# rapidshark-main-breakout-top-mk-1_4.net
KiCad netlist of a schematic drawn in EAGLE
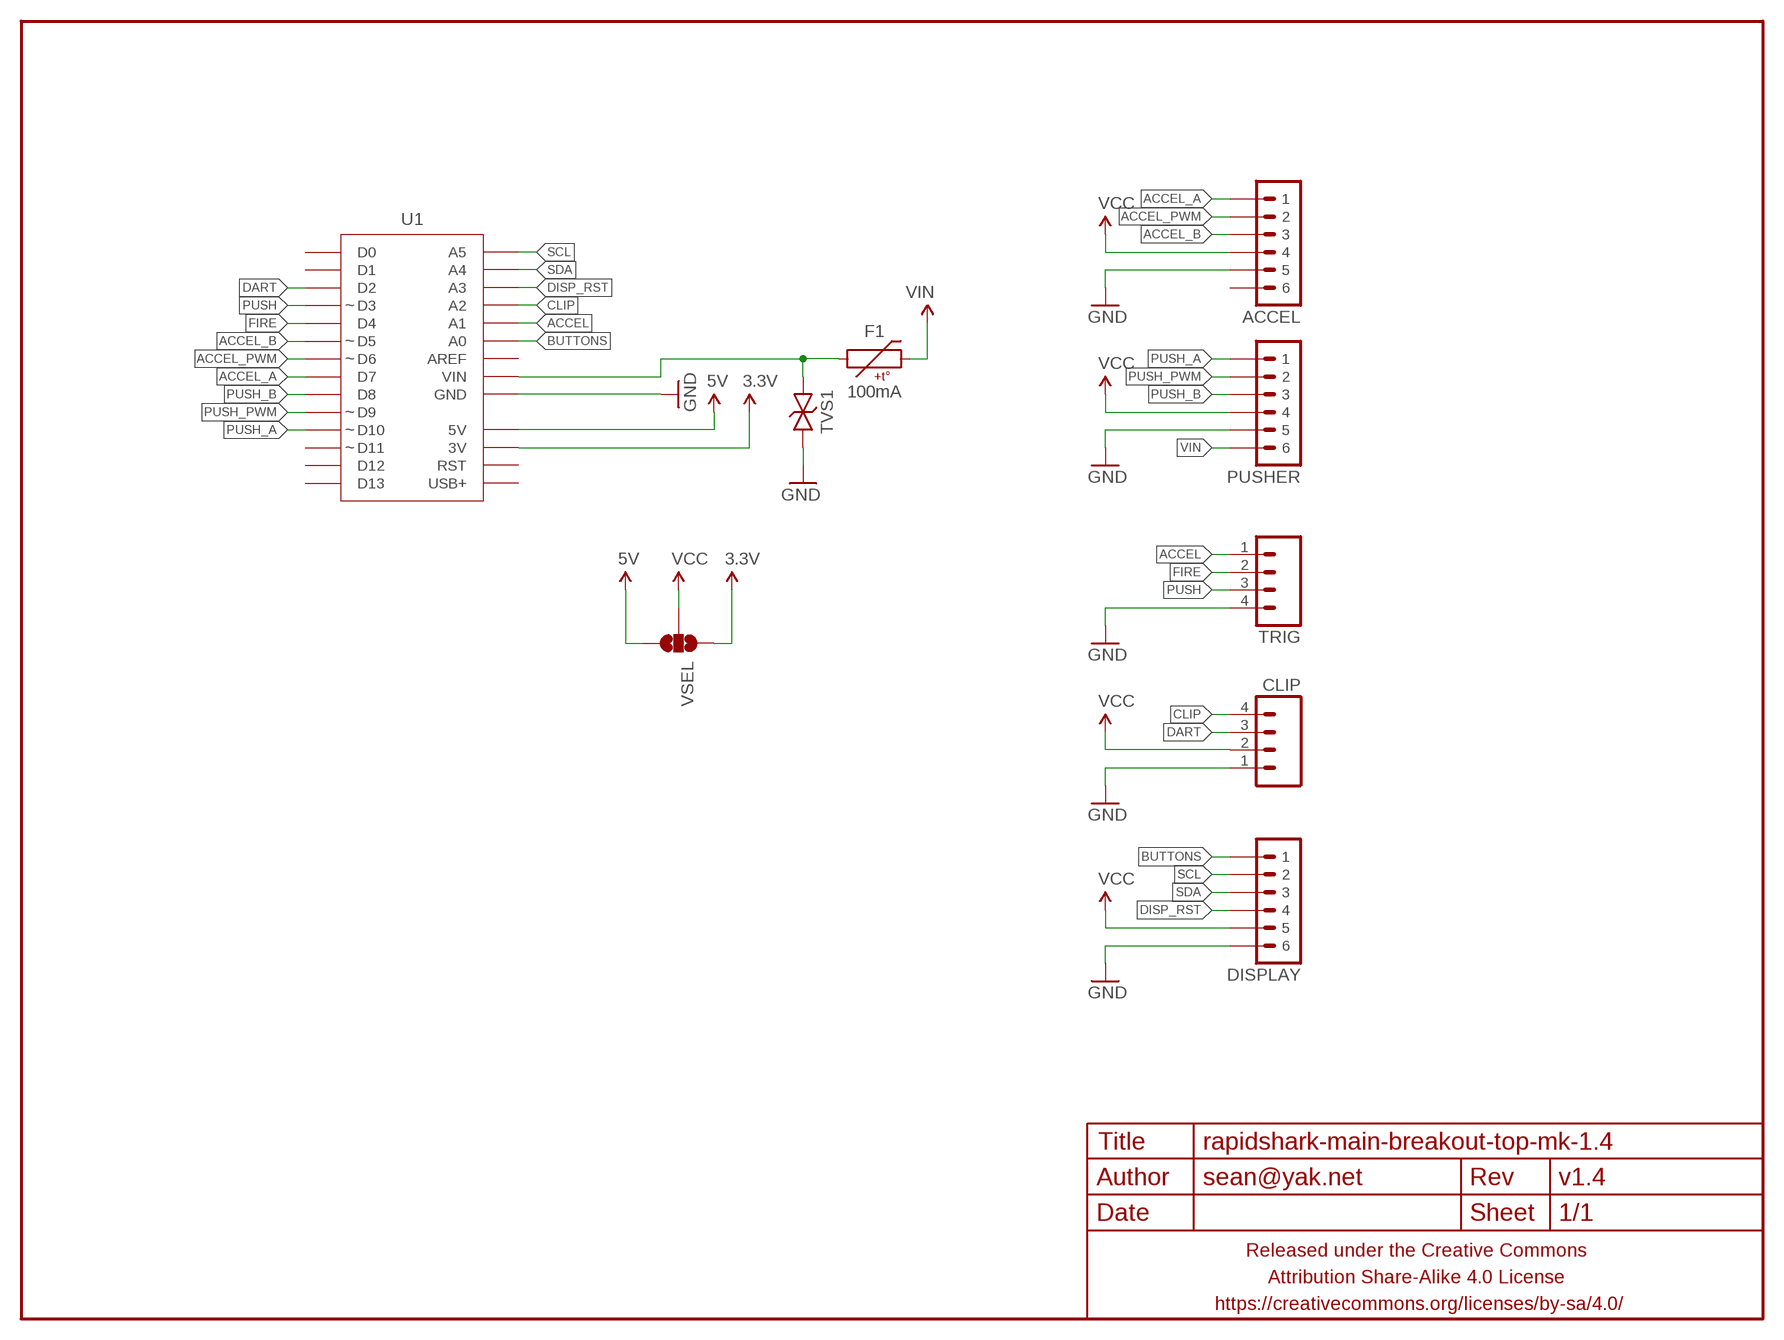
[diagram p0: schematic, sheet 1]

(export (version "E")
  (design (tool "Eeschema 10.0.6"))
  (components
    (comp (ref "ACCEL")
      (value "M06JST-PH-PTH-VERT")
      (footprint "eagle-import:JST-6-PH-VERT-PTH")
      (libsource (lib "eagle-import") (part "M06JST-PH-PTH-VERT"))
    )
    (comp (ref "CLIP")
      (value "M04JST-PTH-VERT")
      (footprint "eagle-import:JST-4-PH-VERT-PTH")
      (libsource (lib "eagle-import") (part "M04JST-PTH-VERT"))
    )
    (comp (ref "DISPLAY")
      (value "M06JST-PH-PTH-VERT")
      (footprint "eagle-import:JST-6-PH-VERT-PTH")
      (libsource (lib "eagle-import") (part "M06JST-PH-PTH-VERT"))
    )
    (comp (ref "F1")
      (value "100mA")
      (footprint "eagle-import:PTC-1206")
      (libsource (lib "eagle-import") (part "PTCSMD"))
    )
    (comp (ref "FRAME1")
      (value "FRAME-LETTERNO_PACKAGE")
      (footprint "eagle-import:DUMMY")
      (fields (field (name "DESIGNER") "sean@yak.net") (field (name "VERSION") "v1.4"))
      (libsource (lib "eagle-import") (part "FRAME-LETTERNO_PACKAGE"))
    )
    (comp (ref "PUSHER")
      (value "M06JST-PH-PTH-VERT")
      (footprint "eagle-import:JST-6-PH-VERT-PTH")
      (libsource (lib "eagle-import") (part "M06JST-PH-PTH-VERT"))
    )
    (comp (ref "TRIG")
      (value "M04JST-PTH-VERT")
      (footprint "eagle-import:JST-4-PH-VERT-PTH")
      (libsource (lib "eagle-import") (part "M04JST-PTH-VERT"))
    )
    (comp (ref "TVS1")
      (value "TVSDO-41-8.89MM")
      (footprint "eagle-import:DO-41-TVS-BI-8.89MM")
      (libsource (lib "eagle-import") (part "TVSDO-41-8.89MM"))
    )
    (comp (ref "U1")
      (value "ADAFRUIT_METRO_MININOSILK-AMBI2")
      (footprint "eagle-import:ADAFRUIT_METRO_MINI_BACK")
      (libsource (lib "eagle-import") (part "ADAFRUIT_METRO_MININOSILK-AMBI2"))
    )
    (comp (ref "VSEL")
      (value "JUMPER-PAD-3-NOFULL_BOX_SILK")
      (footprint "eagle-import:PAD-JUMPER-3-NO_YES_SILK_FULL_BOX")
      (libsource (lib "eagle-import") (part "JUMPER-PAD-3-NOFULL_BOX_SILK"))
    )
  )
  (nets
    (net (code "1") (name "3.3V") (class "Default")
      (node (ref "U1") (pin "17") (pinfunction "3V_17") (pintype "bidirectional"))
      (node (ref "VSEL") (pin "1") (pinfunction "1_1") (pintype "passive"))
    )
    (net (code "2") (name "5V") (class "Default")
      (node (ref "U1") (pin "18") (pinfunction "5V_18") (pintype "bidirectional"))
      (node (ref "VSEL") (pin "3") (pinfunction "3_3") (pintype "passive"))
    )
    (net (code "3") (name "ACCEL") (class "Default")
      (node (ref "TRIG") (pin "1") (pinfunction "1_1") (pintype "passive"))
      (node (ref "U1") (pin "24") (pinfunction "A1_24") (pintype "bidirectional"))
    )
    (net (code "4") (name "ACCEL_A") (class "Default")
      (node (ref "ACCEL") (pin "1") (pinfunction "1_1") (pintype "passive"))
      (node (ref "U1") (pin "8") (pinfunction "D7_8") (pintype "bidirectional"))
    )
    (net (code "5") (name "ACCEL_B") (class "Default")
      (node (ref "ACCEL") (pin "3") (pinfunction "3_3") (pintype "passive"))
      (node (ref "U1") (pin "6") (pinfunction "D5_6") (pintype "bidirectional"))
    )
    (net (code "6") (name "ACCEL_PWM") (class "Default")
      (node (ref "ACCEL") (pin "2") (pinfunction "2_2") (pintype "passive"))
      (node (ref "U1") (pin "7") (pinfunction "D6_7") (pintype "bidirectional"))
    )
    (net (code "7") (name "BUTTONS") (class "Default")
      (node (ref "DISPLAY") (pin "1") (pinfunction "1_1") (pintype "passive"))
      (node (ref "U1") (pin "23") (pinfunction "A0_23") (pintype "bidirectional"))
    )
    (net (code "8") (name "CLIP") (class "Default")
      (node (ref "CLIP") (pin "4") (pinfunction "4_4") (pintype "passive"))
      (node (ref "U1") (pin "25") (pinfunction "A2_25") (pintype "bidirectional"))
    )
    (net (code "9") (name "DART") (class "Default")
      (node (ref "CLIP") (pin "3") (pinfunction "3_3") (pintype "passive"))
      (node (ref "U1") (pin "3") (pinfunction "D2_3") (pintype "bidirectional"))
    )
    (net (code "10") (name "DISP_RST") (class "Default")
      (node (ref "DISPLAY") (pin "4") (pinfunction "4_4") (pintype "passive"))
      (node (ref "U1") (pin "26") (pinfunction "A3_26") (pintype "bidirectional"))
    )
    (net (code "11") (name "FIRE") (class "Default")
      (node (ref "TRIG") (pin "2") (pinfunction "2_2") (pintype "passive"))
      (node (ref "U1") (pin "5") (pinfunction "D4_5") (pintype "bidirectional"))
    )
    (net (code "12") (name "GND") (class "Default")
      (node (ref "ACCEL") (pin "5") (pinfunction "5_5") (pintype "passive"))
      (node (ref "CLIP") (pin "1") (pinfunction "1_1") (pintype "passive"))
      (node (ref "DISPLAY") (pin "6") (pinfunction "6_6") (pintype "passive"))
      (node (ref "PUSHER") (pin "5") (pinfunction "5_5") (pintype "passive"))
      (node (ref "TRIG") (pin "4") (pinfunction "4_4") (pintype "passive"))
      (node (ref "TVS1") (pin "P$1") (pinfunction "1_P$1") (pintype "passive"))
      (node (ref "U1") (pin "19") (pinfunction "GND_19") (pintype "bidirectional"))
      (node (ref "U1") (pin "20") (pinfunction "GND_20") (pintype "bidirectional"))
    )
    (net (code "13") (name "Net-(TVS1-2)") (class "Default")
      (node (ref "F1") (pin "1") (pinfunction "1_1") (pintype "passive"))
      (node (ref "TVS1") (pin "P$2") (pinfunction "2_P$2") (pintype "passive"))
      (node (ref "U1") (pin "21") (pinfunction "VIN_21") (pintype "bidirectional"))
    )
    (net (code "14") (name "PUSH") (class "Default")
      (node (ref "TRIG") (pin "3") (pinfunction "3_3") (pintype "passive"))
      (node (ref "U1") (pin "4") (pinfunction "D3_4") (pintype "bidirectional"))
    )
    (net (code "15") (name "PUSH_A") (class "Default")
      (node (ref "PUSHER") (pin "1") (pinfunction "1_1") (pintype "passive"))
      (node (ref "U1") (pin "11") (pinfunction "D10_11") (pintype "bidirectional"))
    )
    (net (code "16") (name "PUSH_B") (class "Default")
      (node (ref "PUSHER") (pin "3") (pinfunction "3_3") (pintype "passive"))
      (node (ref "U1") (pin "9") (pinfunction "D8_9") (pintype "bidirectional"))
    )
    (net (code "17") (name "PUSH_PWM") (class "Default")
      (node (ref "PUSHER") (pin "2") (pinfunction "2_2") (pintype "passive"))
      (node (ref "U1") (pin "10") (pinfunction "D9_10") (pintype "bidirectional"))
    )
    (net (code "18") (name "SCL") (class "Default")
      (node (ref "DISPLAY") (pin "2") (pinfunction "2_2") (pintype "passive"))
      (node (ref "U1") (pin "28") (pinfunction "A5_28") (pintype "bidirectional"))
    )
    (net (code "19") (name "SDA") (class "Default")
      (node (ref "DISPLAY") (pin "3") (pinfunction "3_3") (pintype "passive"))
      (node (ref "U1") (pin "27") (pinfunction "A4_27") (pintype "bidirectional"))
    )
    (net (code "20") (name "VCC") (class "Default")
      (node (ref "ACCEL") (pin "4") (pinfunction "4_4") (pintype "passive"))
      (node (ref "CLIP") (pin "2") (pinfunction "2_2") (pintype "passive"))
      (node (ref "DISPLAY") (pin "5") (pinfunction "5_5") (pintype "passive"))
      (node (ref "PUSHER") (pin "4") (pinfunction "4_4") (pintype "passive"))
      (node (ref "VSEL") (pin "2") (pinfunction "2_2") (pintype "passive"))
    )
    (net (code "21") (name "VIN") (class "Default")
      (node (ref "F1") (pin "2") (pinfunction "2_2") (pintype "passive"))
      (node (ref "PUSHER") (pin "6") (pinfunction "6_6") (pintype "passive"))
    )
    (net (code "22") (name "unconnected-(ACCEL-Pad6)") (class "Default")
      (node (ref "ACCEL") (pin "6") (pinfunction "6_6") (pintype "passive"))
    )
    (net (code "23") (name "unconnected-(U1-AREF-Pad22)") (class "Default")
      (node (ref "U1") (pin "22") (pinfunction "AREF_22") (pintype "bidirectional"))
    )
    (net (code "24") (name "unconnected-(U1-D0-Pad1)") (class "Default")
      (node (ref "U1") (pin "1") (pinfunction "D0_1") (pintype "bidirectional"))
    )
    (net (code "25") (name "unconnected-(U1-D1-Pad2)") (class "Default")
      (node (ref "U1") (pin "2") (pinfunction "D1_2") (pintype "bidirectional"))
    )
    (net (code "26") (name "unconnected-(U1-D11-Pad12)") (class "Default")
      (node (ref "U1") (pin "12") (pinfunction "D11_12") (pintype "bidirectional"))
    )
    (net (code "27") (name "unconnected-(U1-D12-Pad13)") (class "Default")
      (node (ref "U1") (pin "13") (pinfunction "D12_13") (pintype "bidirectional"))
    )
    (net (code "28") (name "unconnected-(U1-D13-Pad14)") (class "Default")
      (node (ref "U1") (pin "14") (pinfunction "D13_14") (pintype "bidirectional"))
    )
    (net (code "29") (name "unconnected-(U1-RST-Pad16)") (class "Default")
      (node (ref "U1") (pin "16") (pinfunction "RST_16") (pintype "bidirectional"))
    )
    (net (code "30") (name "unconnected-(U1-USB+-Pad15)") (class "Default")
      (node (ref "U1") (pin "15") (pinfunction "USB+_15") (pintype "bidirectional"))
    )
  )
)
